# 01_TOP_LEVEL.net
KiCad netlist of a schematic drawn in Altium Designer
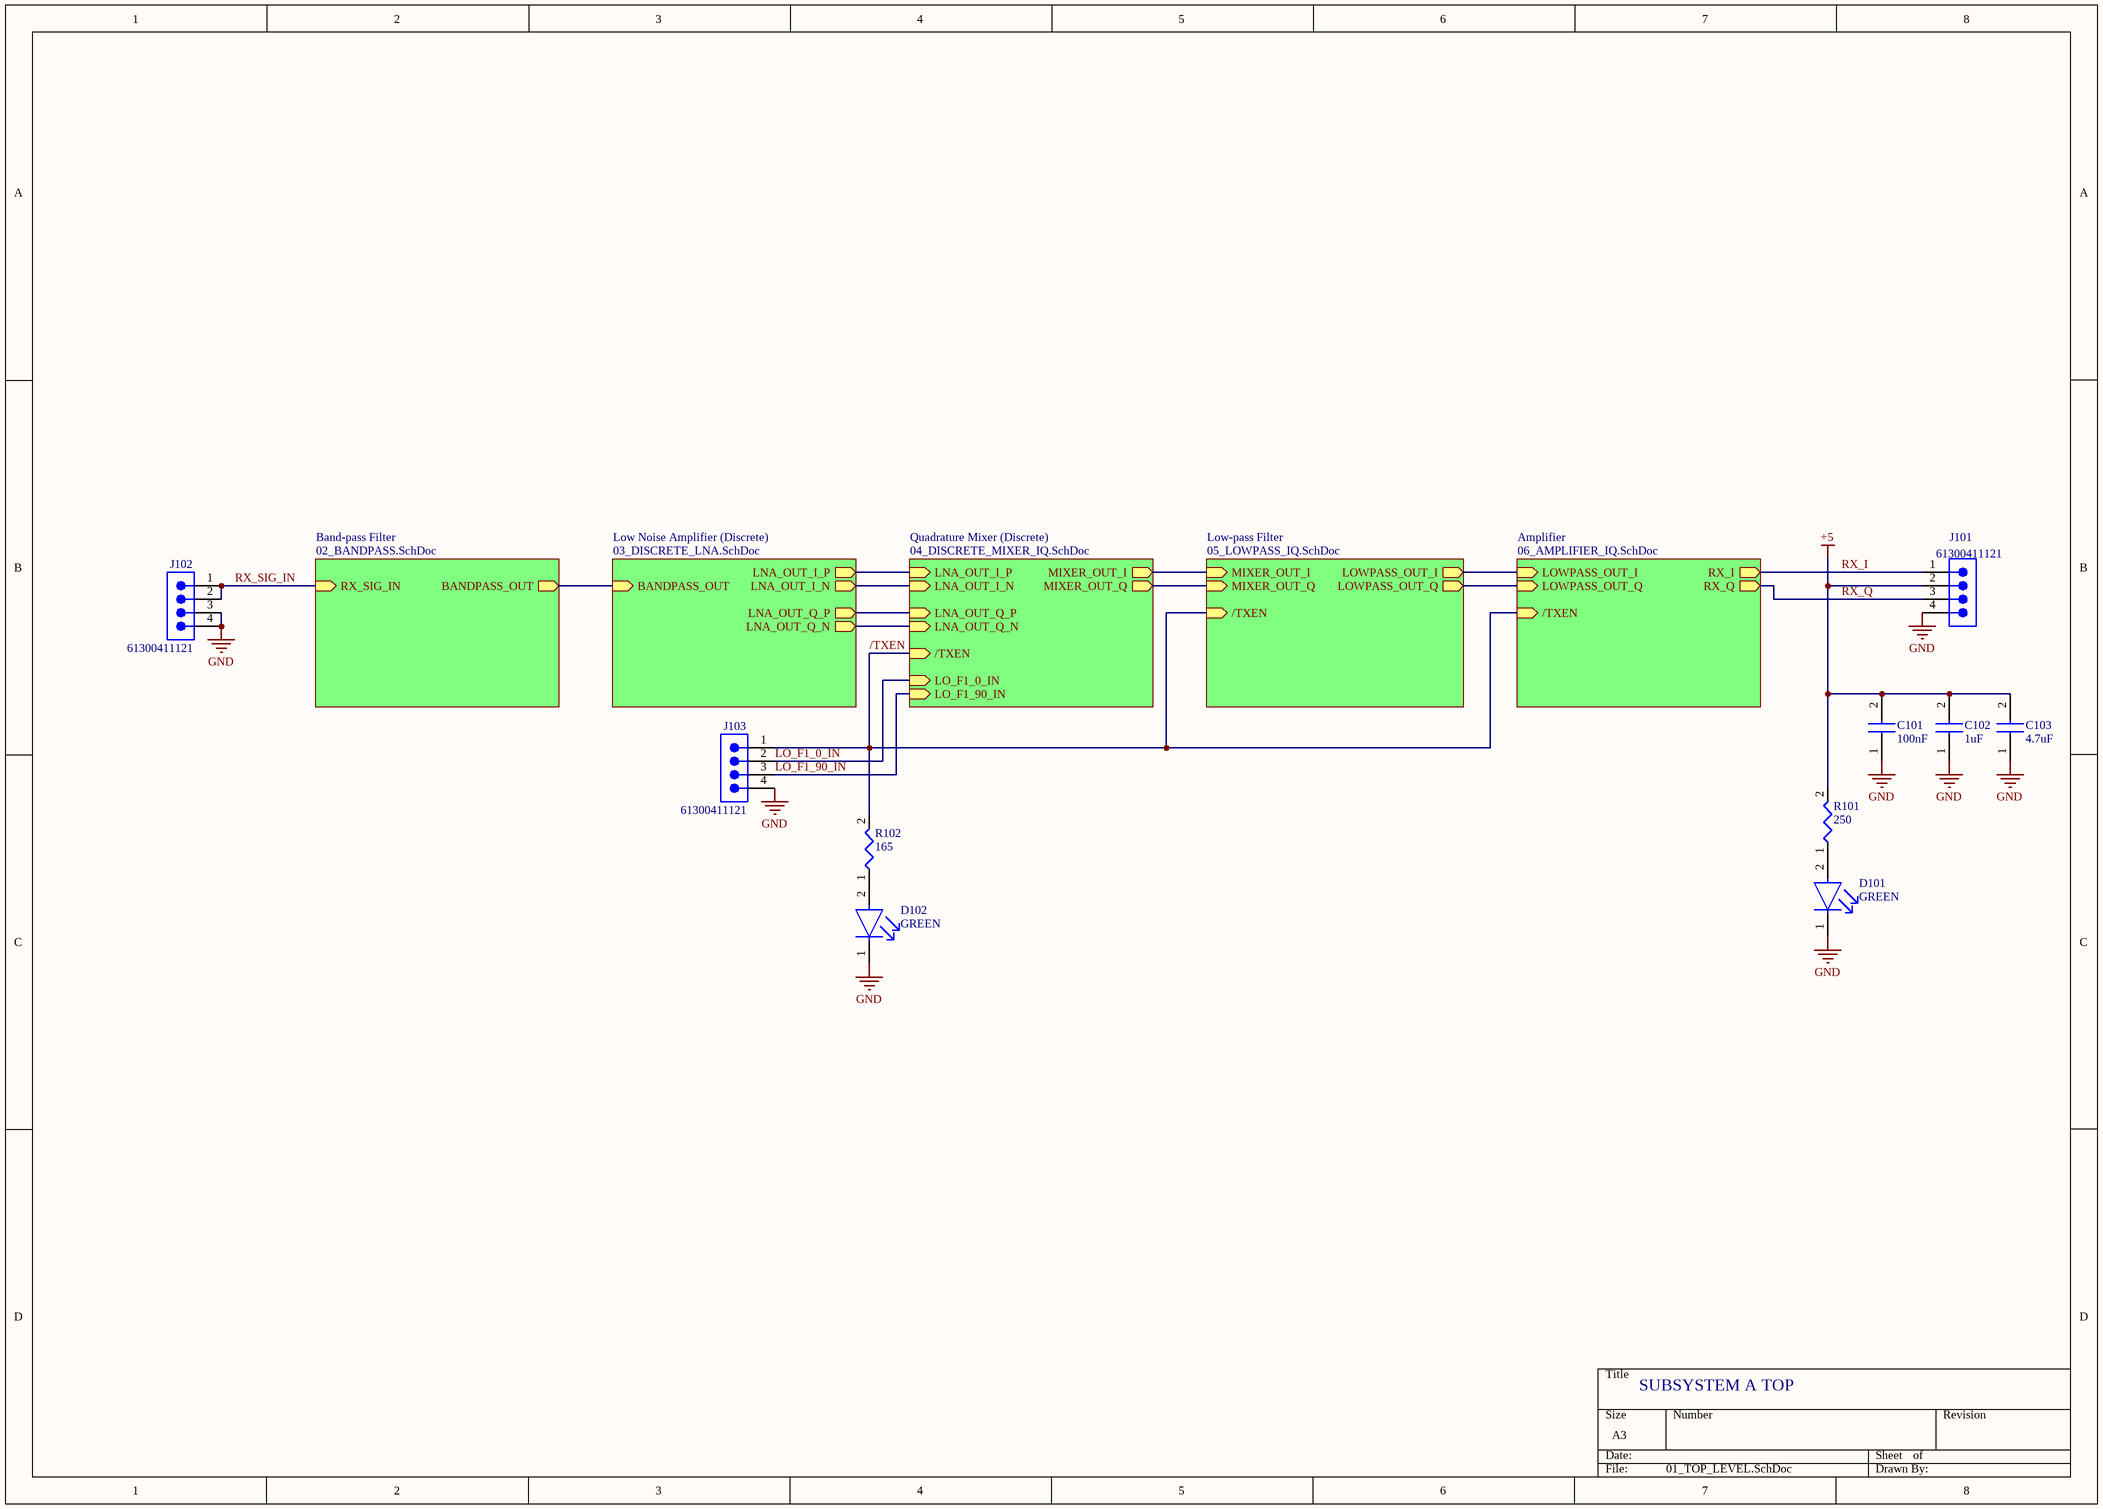
[diagram p0: 01_TOP_LEVEL.SchDoc]

(export (version "E")
  (design (tool "Eeschema 10.0.6"))
  (components
    (comp (ref "C101")
      (value "100nF")
      (footprint "CAP_0805")
      (description "Capacitor SMD 0805")
      (libsource (lib "Passive_Components") (part "CAP_0805"))
    )
    (comp (ref "C102")
      (value "1uF")
      (footprint "CAP_0805")
      (description "Capacitor SMD 0805")
      (libsource (lib "Passive_Components") (part "CAP_0805"))
    )
    (comp (ref "C103")
      (value "4.7uF")
      (footprint "CAP_0805")
      (description "Capacitor SMD 0805")
      (libsource (lib "Passive_Components") (part "CAP_0805"))
    )
    (comp (ref "D101")
      (value "GREEN")
      (footprint "FP-LTST-C170GKT-MFG")
      (description "LED GREEN CLEAR SMD")
      (fields (field (name "VOLTAGE") "5V"))
      (libsource (lib "Altium Content Vault") (part "8706943c75ba83719d021d2fdc84c58"))
    )
    (comp (ref "D102")
      (value "GREEN")
      (footprint "FP-LTST-C170GKT-MFG")
      (description "LED GREEN CLEAR SMD")
      (fields (field (name "VOLTAGE") "5V"))
      (libsource (lib "Altium Content Vault") (part "8706943c75ba83719d021d2fdc84c58"))
    )
    (comp (ref "J101")
      (value "61300411121")
      (footprint "61300411121")
      (description "THT Vertical Pin Header WR-PHD, Pitch 2.54 mm, Single Row, 4 pins")
      (libsource (lib "Altium Content Vault") (part "Header_Male_1R_04P"))
    )
    (comp (ref "J102")
      (value "61300411121")
      (footprint "61300411121")
      (description "THT Vertical Pin Header WR-PHD, Pitch 2.54 mm, Single Row, 4 pins")
      (libsource (lib "Altium Content Vault") (part "Header_Male_1R_04P"))
    )
    (comp (ref "J103")
      (value "61300411121")
      (footprint "61300411121")
      (description "THT Vertical Pin Header WR-PHD, Pitch 2.54 mm, Single Row, 4 pins")
      (libsource (lib "Altium Content Vault") (part "Header_Male_1R_04P"))
    )
    (comp (ref "R101")
      (value "250")
      (footprint "RES_0805")
      (description "Resistor SMD 0805")
      (libsource (lib "Passive_Components") (part "RES_0805"))
    )
    (comp (ref "R102")
      (value "165")
      (footprint "RES_0805")
      (description "Resistor SMD 0805")
      (libsource (lib "Passive_Components") (part "RES_0805"))
    )
  )
  (nets
    (net (code "1") (name "+5") (class "Default")
      (node (ref "C101") (pin "2") (pinfunction "2_2") (pintype "passive"))
      (node (ref "C102") (pin "2") (pinfunction "2_2") (pintype "passive"))
      (node (ref "C103") (pin "2") (pinfunction "2_2") (pintype "passive"))
      (node (ref "J101") (pin "2") (pinfunction "2_2") (pintype "passive"))
      (node (ref "R101") (pin "2") (pinfunction "2_2") (pintype "passive"))
    )
    (net (code "9") (name "/LO_F1_0_IN") (class "Default")
      (node (ref "J103") (pin "2") (pinfunction "2_2") (pintype "passive"))
    )
    (net (code "10") (name "/LO_F1_90_IN") (class "Default")
      (node (ref "J103") (pin "3") (pinfunction "3_3") (pintype "passive"))
    )
    (net (code "13") (name "/RX_I") (class "Default")
      (node (ref "J101") (pin "1") (pinfunction "1_1") (pintype "passive"))
    )
    (net (code "14") (name "/RX_Q") (class "Default")
      (node (ref "J101") (pin "3") (pinfunction "3_3") (pintype "passive"))
    )
    (net (code "15") (name "/RX_SIG_IN") (class "Default")
      (node (ref "J102") (pin "1") (pinfunction "1_1") (pintype "passive"))
      (node (ref "J102") (pin "2") (pinfunction "2_2") (pintype "passive"))
    )
    (net (code "16") (name "/{slash}TXEN") (class "Default")
      (node (ref "J103") (pin "1") (pinfunction "1_1") (pintype "passive"))
      (node (ref "R102") (pin "2") (pinfunction "2_2") (pintype "passive"))
    )
    (net (code "17") (name "GND") (class "Default")
      (node (ref "C101") (pin "1") (pinfunction "1_1") (pintype "passive"))
      (node (ref "C102") (pin "1") (pinfunction "1_1") (pintype "passive"))
      (node (ref "C103") (pin "1") (pinfunction "1_1") (pintype "passive"))
      (node (ref "D101") (pin "1") (pinfunction "C_1") (pintype "passive"))
      (node (ref "D102") (pin "1") (pinfunction "C_1") (pintype "passive"))
      (node (ref "J101") (pin "4") (pinfunction "4_4") (pintype "passive"))
      (node (ref "J102") (pin "3") (pinfunction "3_3") (pintype "passive"))
      (node (ref "J102") (pin "4") (pinfunction "4_4") (pintype "passive"))
      (node (ref "J103") (pin "4") (pinfunction "4_4") (pintype "passive"))
    )
    (net (code "18") (name "Net-(D101-A)") (class "Default")
      (node (ref "D101") (pin "2") (pinfunction "A_2") (pintype "passive"))
      (node (ref "R101") (pin "1") (pinfunction "1_1") (pintype "passive"))
    )
    (net (code "19") (name "Net-(D102-A)") (class "Default")
      (node (ref "D102") (pin "2") (pinfunction "A_2") (pintype "passive"))
      (node (ref "R102") (pin "1") (pinfunction "1_1") (pintype "passive"))
    )
  )
)
